# GateDriver.net
KiCad netlist of a schematic drawn in Altium Designer
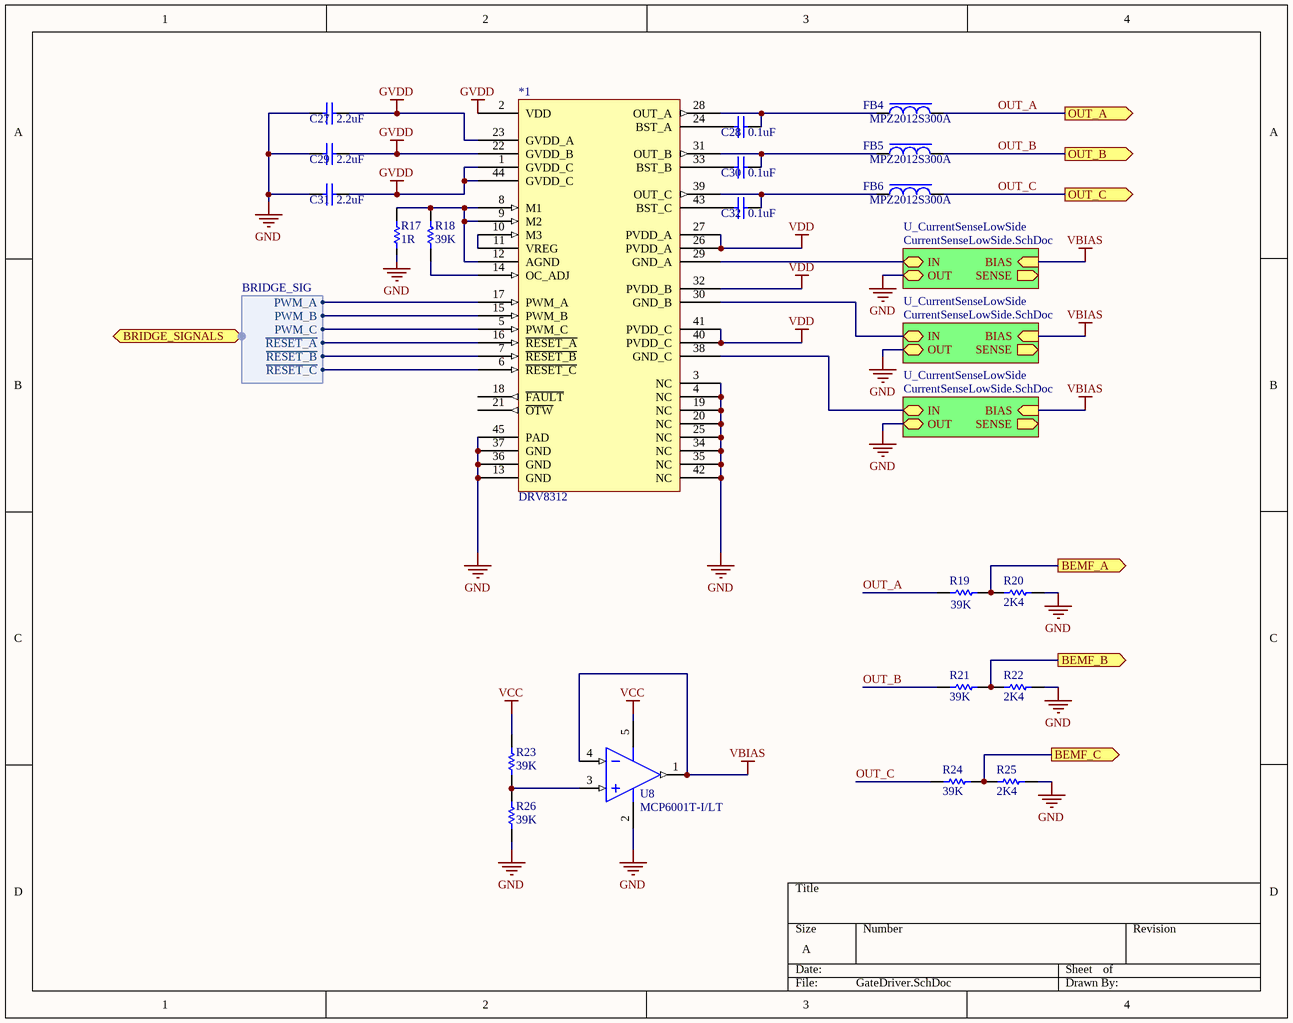
[diagram p0: GateDriver.SchDoc]

(export (version "E")
  (design (tool "Eeschema 10.0.6"))
  (components
    (comp (ref "*1")
      (value "DRV8312")
      (footprint "HTSSOP-44E")
      (libsource (lib "Components") (part "DRV8312"))
    )
    (comp (ref "C27")
      (value "2.2uF")
      (footprint "CAPC0603(1608)100_M")
      (description "CAP 2.2uF 25V ±10% 0603 (1608 Metric) Thickness 1mm SMD")
      (fields (field (name "TOLERANCE") "Â±10%"))
      (libsource (lib "Altium Content Vault") (part "CAP"))
    )
    (comp (ref "C28")
      (value "0.1uF")
      (footprint "CAPC0603(1608)100_L")
      (description "CAP 100nF 100V ±10% 0603 (1608 Metric) Thickness 1mm SMD")
      (fields (field (name "TOLERANCE") "Â±10%"))
      (libsource (lib "Altium Content Vault") (part "CAP"))
    )
    (comp (ref "C29")
      (value "2.2uF")
      (footprint "CAPC0603(1608)100_M")
      (description "CAP 2.2uF 25V ±10% 0603 (1608 Metric) Thickness 1mm SMD")
      (fields (field (name "TOLERANCE") "Â±10%"))
      (libsource (lib "Altium Content Vault") (part "CAP"))
    )
    (comp (ref "C30")
      (value "0.1uF")
      (footprint "CAPC0603(1608)100_L")
      (description "CAP 100nF 100V ±10% 0603 (1608 Metric) Thickness 1mm SMD")
      (fields (field (name "TOLERANCE") "Â±10%"))
      (libsource (lib "Altium Content Vault") (part "CAP"))
    )
    (comp (ref "C31")
      (value "2.2uF")
      (footprint "CAPC0603(1608)100_M")
      (description "CAP 2.2uF 25V ±10% 0603 (1608 Metric) Thickness 1mm SMD")
      (fields (field (name "TOLERANCE") "Â±10%"))
      (libsource (lib "Altium Content Vault") (part "CAP"))
    )
    (comp (ref "C32")
      (value "0.1uF")
      (footprint "CAPC0603(1608)100_L")
      (description "CAP 100nF 100V ±10% 0603 (1608 Metric) Thickness 1mm SMD")
      (fields (field (name "TOLERANCE") "Â±10%"))
      (libsource (lib "Altium Content Vault") (part "CAP"))
    )
    (comp (ref "FB4")
      (value "MPZ2012S300A")
      (footprint "0805-Ferrite")
      (libsource (lib "Components") (part "MPZ2012S300A"))
    )
    (comp (ref "FB5")
      (value "MPZ2012S300A")
      (footprint "0805-Ferrite")
      (libsource (lib "Components") (part "MPZ2012S300A"))
    )
    (comp (ref "FB6")
      (value "MPZ2012S300A")
      (footprint "0805-Ferrite")
      (libsource (lib "Components") (part "MPZ2012S300A"))
    )
    (comp (ref "R17")
      (value "1R")
      (footprint "RESC0603(1608)_M")
      (description "1R 0.1W 5% 0603 (1608 Metric)  SMD")
      (fields (field (name "POWER") "0.1 W") (field (name "TOLERANCE") "5 %"))
      (libsource (lib "Altium Content Vault") (part "RES"))
    )
    (comp (ref "R18")
      (value "39K")
      (footprint "RESC0603(1608)_M")
      (description "39K 0.1W 1% 0603 (1608 Metric)  SMD")
      (fields (field (name "TOLERANCE") "1 %") (field (name "POWER") "0.1 W"))
      (libsource (lib "Altium Content Vault") (part "RES"))
    )
    (comp (ref "R19")
      (value "39K")
      (footprint "RESC0603(1608)_M")
      (description "39K 0.1W 1% 0603 (1608 Metric)  SMD")
      (fields (field (name "TOLERANCE") "1 %") (field (name "POWER") "0.1 W"))
      (libsource (lib "Altium Content Vault") (part "RES"))
    )
    (comp (ref "R20")
      (value "2K4")
      (footprint "RESC0603(1608)_L")
      (description "2K4 0.1W 1% 0603 (1608 Metric)  SMD")
      (fields (field (name "TOLERANCE") "1 %") (field (name "POWER") "0.1 W"))
      (libsource (lib "Altium Content Vault") (part "RES"))
    )
    (comp (ref "R21")
      (value "39K")
      (footprint "RESC0603(1608)_M")
      (description "39K 0.1W 1% 0603 (1608 Metric)  SMD")
      (fields (field (name "TOLERANCE") "1 %") (field (name "POWER") "0.1 W"))
      (libsource (lib "Altium Content Vault") (part "RES"))
    )
    (comp (ref "R22")
      (value "2K4")
      (footprint "RESC0603(1608)_L")
      (description "2K4 0.1W 1% 0603 (1608 Metric)  SMD")
      (fields (field (name "TOLERANCE") "1 %") (field (name "POWER") "0.1 W"))
      (libsource (lib "Altium Content Vault") (part "RES"))
    )
    (comp (ref "R23")
      (value "39K")
      (footprint "RESC0603(1608)_M")
      (description "39K 0.1W 1% 0603 (1608 Metric)  SMD")
      (fields (field (name "TOLERANCE") "1 %") (field (name "POWER") "0.1 W"))
      (libsource (lib "Altium Content Vault") (part "RES"))
    )
    (comp (ref "R24")
      (value "39K")
      (footprint "RESC0603(1608)_M")
      (description "39K 0.1W 1% 0603 (1608 Metric)  SMD")
      (fields (field (name "TOLERANCE") "1 %") (field (name "POWER") "0.1 W"))
      (libsource (lib "Altium Content Vault") (part "RES"))
    )
    (comp (ref "R25")
      (value "2K4")
      (footprint "RESC0603(1608)_L")
      (description "2K4 0.1W 1% 0603 (1608 Metric)  SMD")
      (fields (field (name "TOLERANCE") "1 %") (field (name "POWER") "0.1 W"))
      (libsource (lib "Altium Content Vault") (part "RES"))
    )
    (comp (ref "R26")
      (value "39K")
      (footprint "RESC0603(1608)_M")
      (description "39K 0.1W 1% 0603 (1608 Metric)  SMD")
      (fields (field (name "TOLERANCE") "1 %") (field (name "POWER") "0.1 W"))
      (libsource (lib "Altium Content Vault") (part "RES"))
    )
    (comp (ref "U8")
      (value "MCP6001T-I/LT")
      (footprint "SC70-LT5_M")
      (description "1 MHz, Low-Power Operational Amplifier, 5-Pin SC-70, Industrial Temperature, Tape and Reel")
      (libsource (lib "Altium Content Vault") (part "AMP-OPA-MCP6001-SOT5"))
    )
  )
  (nets
    (net (code "2") (name "/BEMF_A") (class "Default")
      (node (ref "R19") (pin "1") (pinfunction "1_1") (pintype "passive"))
      (node (ref "R20") (pin "2") (pinfunction "2_2") (pintype "passive"))
    )
    (net (code "3") (name "/BEMF_B") (class "Default")
      (node (ref "R21") (pin "1") (pinfunction "1_1") (pintype "passive"))
      (node (ref "R22") (pin "2") (pinfunction "2_2") (pintype "passive"))
    )
    (net (code "4") (name "/BEMF_C") (class "Default")
      (node (ref "R24") (pin "1") (pinfunction "1_1") (pintype "passive"))
      (node (ref "R25") (pin "2") (pinfunction "2_2") (pintype "passive"))
    )
    (net (code "5") (name "/IN") (class "Default")
      (node (ref "*1") (pin "38") (pinfunction "GND_C_38") (pintype "power_in"))
    )
    (net (code "6") (name "/IN_1") (class "Default")
      (node (ref "*1") (pin "29") (pinfunction "GND_A_29") (pintype "power_in"))
    )
    (net (code "7") (name "/IN_2") (class "Default")
      (node (ref "*1") (pin "30") (pinfunction "GND_B_30") (pintype "power_in"))
    )
    (net (code "8") (name "/OUT_A") (class "Default")
      (node (ref "FB4") (pin "2") (pinfunction "2_2") (pintype "passive"))
      (node (ref "R19") (pin "2") (pinfunction "2_2") (pintype "passive"))
    )
    (net (code "9") (name "/OUT_B") (class "Default")
      (node (ref "FB5") (pin "2") (pinfunction "2_2") (pintype "passive"))
      (node (ref "R21") (pin "2") (pinfunction "2_2") (pintype "passive"))
    )
    (net (code "10") (name "/OUT_C") (class "Default")
      (node (ref "FB6") (pin "2") (pinfunction "2_2") (pintype "passive"))
      (node (ref "R24") (pin "2") (pinfunction "2_2") (pintype "passive"))
    )
    (net (code "11") (name "/PWM_A") (class "Default")
      (node (ref "*1") (pin "17") (pinfunction "PWM_A_17") (pintype "input"))
    )
    (net (code "12") (name "/PWM_B") (class "Default")
      (node (ref "*1") (pin "15") (pinfunction "PWM_B_15") (pintype "input"))
    )
    (net (code "13") (name "/PWM_C") (class "Default")
      (node (ref "*1") (pin "5") (pinfunction "PWM_C_5") (pintype "input"))
    )
    (net (code "18") (name "/~{RESET_A}") (class "Default")
      (node (ref "*1") (pin "16") (pinfunction "~{RESET_A}_16") (pintype "input"))
    )
    (net (code "19") (name "/~{RESET_B}") (class "Default")
      (node (ref "*1") (pin "7") (pinfunction "~{RESET_B}_7") (pintype "input"))
    )
    (net (code "20") (name "/~{RESET_C}") (class "Default")
      (node (ref "*1") (pin "6") (pinfunction "~{RESET_C}_6") (pintype "input"))
    )
    (net (code "21") (name "GND") (class "Default")
      (node (ref "*1") (pin "13") (pinfunction "GND_13") (pintype "power_in"))
      (node (ref "*1") (pin "19") (pinfunction "NC_19") (pintype "passive"))
      (node (ref "*1") (pin "20") (pinfunction "NC_20") (pintype "passive"))
      (node (ref "*1") (pin "25") (pinfunction "NC_25") (pintype "passive"))
      (node (ref "*1") (pin "3") (pinfunction "NC_3") (pintype "passive"))
      (node (ref "*1") (pin "34") (pinfunction "NC_34") (pintype "passive"))
      (node (ref "*1") (pin "35") (pinfunction "NC_35") (pintype "passive"))
      (node (ref "*1") (pin "36") (pinfunction "GND_36") (pintype "power_in"))
      (node (ref "*1") (pin "37") (pinfunction "GND_37") (pintype "power_in"))
      (node (ref "*1") (pin "4") (pinfunction "NC_4") (pintype "passive"))
      (node (ref "*1") (pin "42") (pinfunction "NC_42") (pintype "passive"))
      (node (ref "*1") (pin "45") (pinfunction "PAD_45") (pintype "power_in"))
      (node (ref "C27") (pin "2") (pinfunction "2_2") (pintype "passive"))
      (node (ref "C29") (pin "2") (pinfunction "2_2") (pintype "passive"))
      (node (ref "C31") (pin "2") (pinfunction "2_2") (pintype "passive"))
      (node (ref "R17") (pin "2") (pinfunction "2_2") (pintype "passive"))
      (node (ref "R20") (pin "1") (pinfunction "1_1") (pintype "passive"))
      (node (ref "R22") (pin "1") (pinfunction "1_1") (pintype "passive"))
      (node (ref "R25") (pin "1") (pinfunction "1_1") (pintype "passive"))
      (node (ref "R26") (pin "1") (pinfunction "1_1") (pintype "passive"))
      (node (ref "U8") (pin "2") (pinfunction "VSS_2") (pintype "power_in"))
    )
    (net (code "22") (name "GVDD") (class "Default")
      (node (ref "*1") (pin "1") (pinfunction "GVDD_C_1") (pintype "power_in"))
      (node (ref "*1") (pin "2") (pinfunction "VDD_2") (pintype "power_in"))
      (node (ref "*1") (pin "22") (pinfunction "GVDD_B_22") (pintype "power_in"))
      (node (ref "*1") (pin "23") (pinfunction "GVDD_A_23") (pintype "power_in"))
      (node (ref "*1") (pin "44") (pinfunction "GVDD_C_44") (pintype "power_in"))
      (node (ref "C27") (pin "1") (pinfunction "1_1") (pintype "passive"))
      (node (ref "C29") (pin "1") (pinfunction "1_1") (pintype "passive"))
      (node (ref "C31") (pin "1") (pinfunction "1_1") (pintype "passive"))
    )
    (net (code "23") (name "Net-(*1-AGND)") (class "Default")
      (node (ref "*1") (pin "12") (pinfunction "AGND_12") (pintype "power_in"))
      (node (ref "*1") (pin "8") (pinfunction "M1_8") (pintype "input"))
      (node (ref "*1") (pin "9") (pinfunction "M2_9") (pintype "input"))
      (node (ref "R17") (pin "1") (pinfunction "1_1") (pintype "passive"))
      (node (ref "R18") (pin "2") (pinfunction "2_2") (pintype "passive"))
    )
    (net (code "24") (name "Net-(*1-BST_A)") (class "Default")
      (node (ref "*1") (pin "24") (pinfunction "BST_A_24") (pintype "power_in"))
      (node (ref "C28") (pin "1") (pinfunction "1_1") (pintype "passive"))
    )
    (net (code "25") (name "Net-(*1-BST_B)") (class "Default")
      (node (ref "*1") (pin "33") (pinfunction "BST_B_33") (pintype "power_in"))
      (node (ref "C30") (pin "1") (pinfunction "1_1") (pintype "passive"))
    )
    (net (code "26") (name "Net-(*1-BST_C)") (class "Default")
      (node (ref "*1") (pin "43") (pinfunction "BST_C_43") (pintype "power_in"))
      (node (ref "C32") (pin "1") (pinfunction "1_1") (pintype "passive"))
    )
    (net (code "27") (name "Net-(*1-M3)") (class "Default")
      (node (ref "*1") (pin "10") (pinfunction "M3_10") (pintype "input"))
      (node (ref "*1") (pin "11") (pinfunction "VREG_11") (pintype "power_in"))
    )
    (net (code "28") (name "Net-(*1-OC_ADJ)") (class "Default")
      (node (ref "*1") (pin "14") (pinfunction "OC_ADJ_14") (pintype "input"))
      (node (ref "R18") (pin "1") (pinfunction "1_1") (pintype "passive"))
    )
    (net (code "29") (name "Net-(*1-OUT_A)") (class "Default")
      (node (ref "*1") (pin "28") (pinfunction "OUT_A_28") (pintype "output"))
      (node (ref "C28") (pin "2") (pinfunction "2_2") (pintype "passive"))
      (node (ref "FB4") (pin "1") (pinfunction "1_1") (pintype "passive"))
    )
    (net (code "30") (name "Net-(*1-OUT_B)") (class "Default")
      (node (ref "*1") (pin "31") (pinfunction "OUT_B_31") (pintype "output"))
      (node (ref "C30") (pin "2") (pinfunction "2_2") (pintype "passive"))
      (node (ref "FB5") (pin "1") (pinfunction "1_1") (pintype "passive"))
    )
    (net (code "31") (name "Net-(*1-OUT_C)") (class "Default")
      (node (ref "*1") (pin "39") (pinfunction "OUT_C_39") (pintype "output"))
      (node (ref "C32") (pin "2") (pinfunction "2_2") (pintype "passive"))
      (node (ref "FB6") (pin "1") (pinfunction "1_1") (pintype "passive"))
    )
    (net (code "32") (name "Net-(U8-VIN+)") (class "Default")
      (node (ref "R23") (pin "1") (pinfunction "1_1") (pintype "passive"))
      (node (ref "R26") (pin "2") (pinfunction "2_2") (pintype "passive"))
      (node (ref "U8") (pin "3") (pinfunction "VIN+_3") (pintype "input"))
    )
    (net (code "33") (name "VBIAS") (class "Default")
      (node (ref "U8") (pin "1") (pinfunction "VOUT_1") (pintype "output"))
      (node (ref "U8") (pin "4") (pinfunction "VIN-_4") (pintype "input"))
    )
    (net (code "34") (name "VCC") (class "Default")
      (node (ref "R23") (pin "2") (pinfunction "2_2") (pintype "passive"))
      (node (ref "U8") (pin "5") (pinfunction "VDD_5") (pintype "power_in"))
    )
    (net (code "35") (name "VDD") (class "Default")
      (node (ref "*1") (pin "26") (pinfunction "PVDD_A_26") (pintype "power_in"))
      (node (ref "*1") (pin "27") (pinfunction "PVDD_A_27") (pintype "power_in"))
      (node (ref "*1") (pin "32") (pinfunction "PVDD_B_32") (pintype "power_in"))
      (node (ref "*1") (pin "40") (pinfunction "PVDD_C_40") (pintype "power_in"))
      (node (ref "*1") (pin "41") (pinfunction "PVDD_C_41") (pintype "power_in"))
    )
    (net (code "36") (name "unconnected-(*1-~{FAULT}-Pad18)") (class "Default")
      (node (ref "*1") (pin "18") (pinfunction "~{FAULT}_18") (pintype "output"))
    )
    (net (code "37") (name "unconnected-(*1-~{OTW}-Pad21)") (class "Default")
      (node (ref "*1") (pin "21") (pinfunction "~{OTW}_21") (pintype "output"))
    )
  )
)
